# SAMC21_Xplained_Pro_Arduino_Connectors.net
KiCad netlist of a schematic drawn in Altium Designer
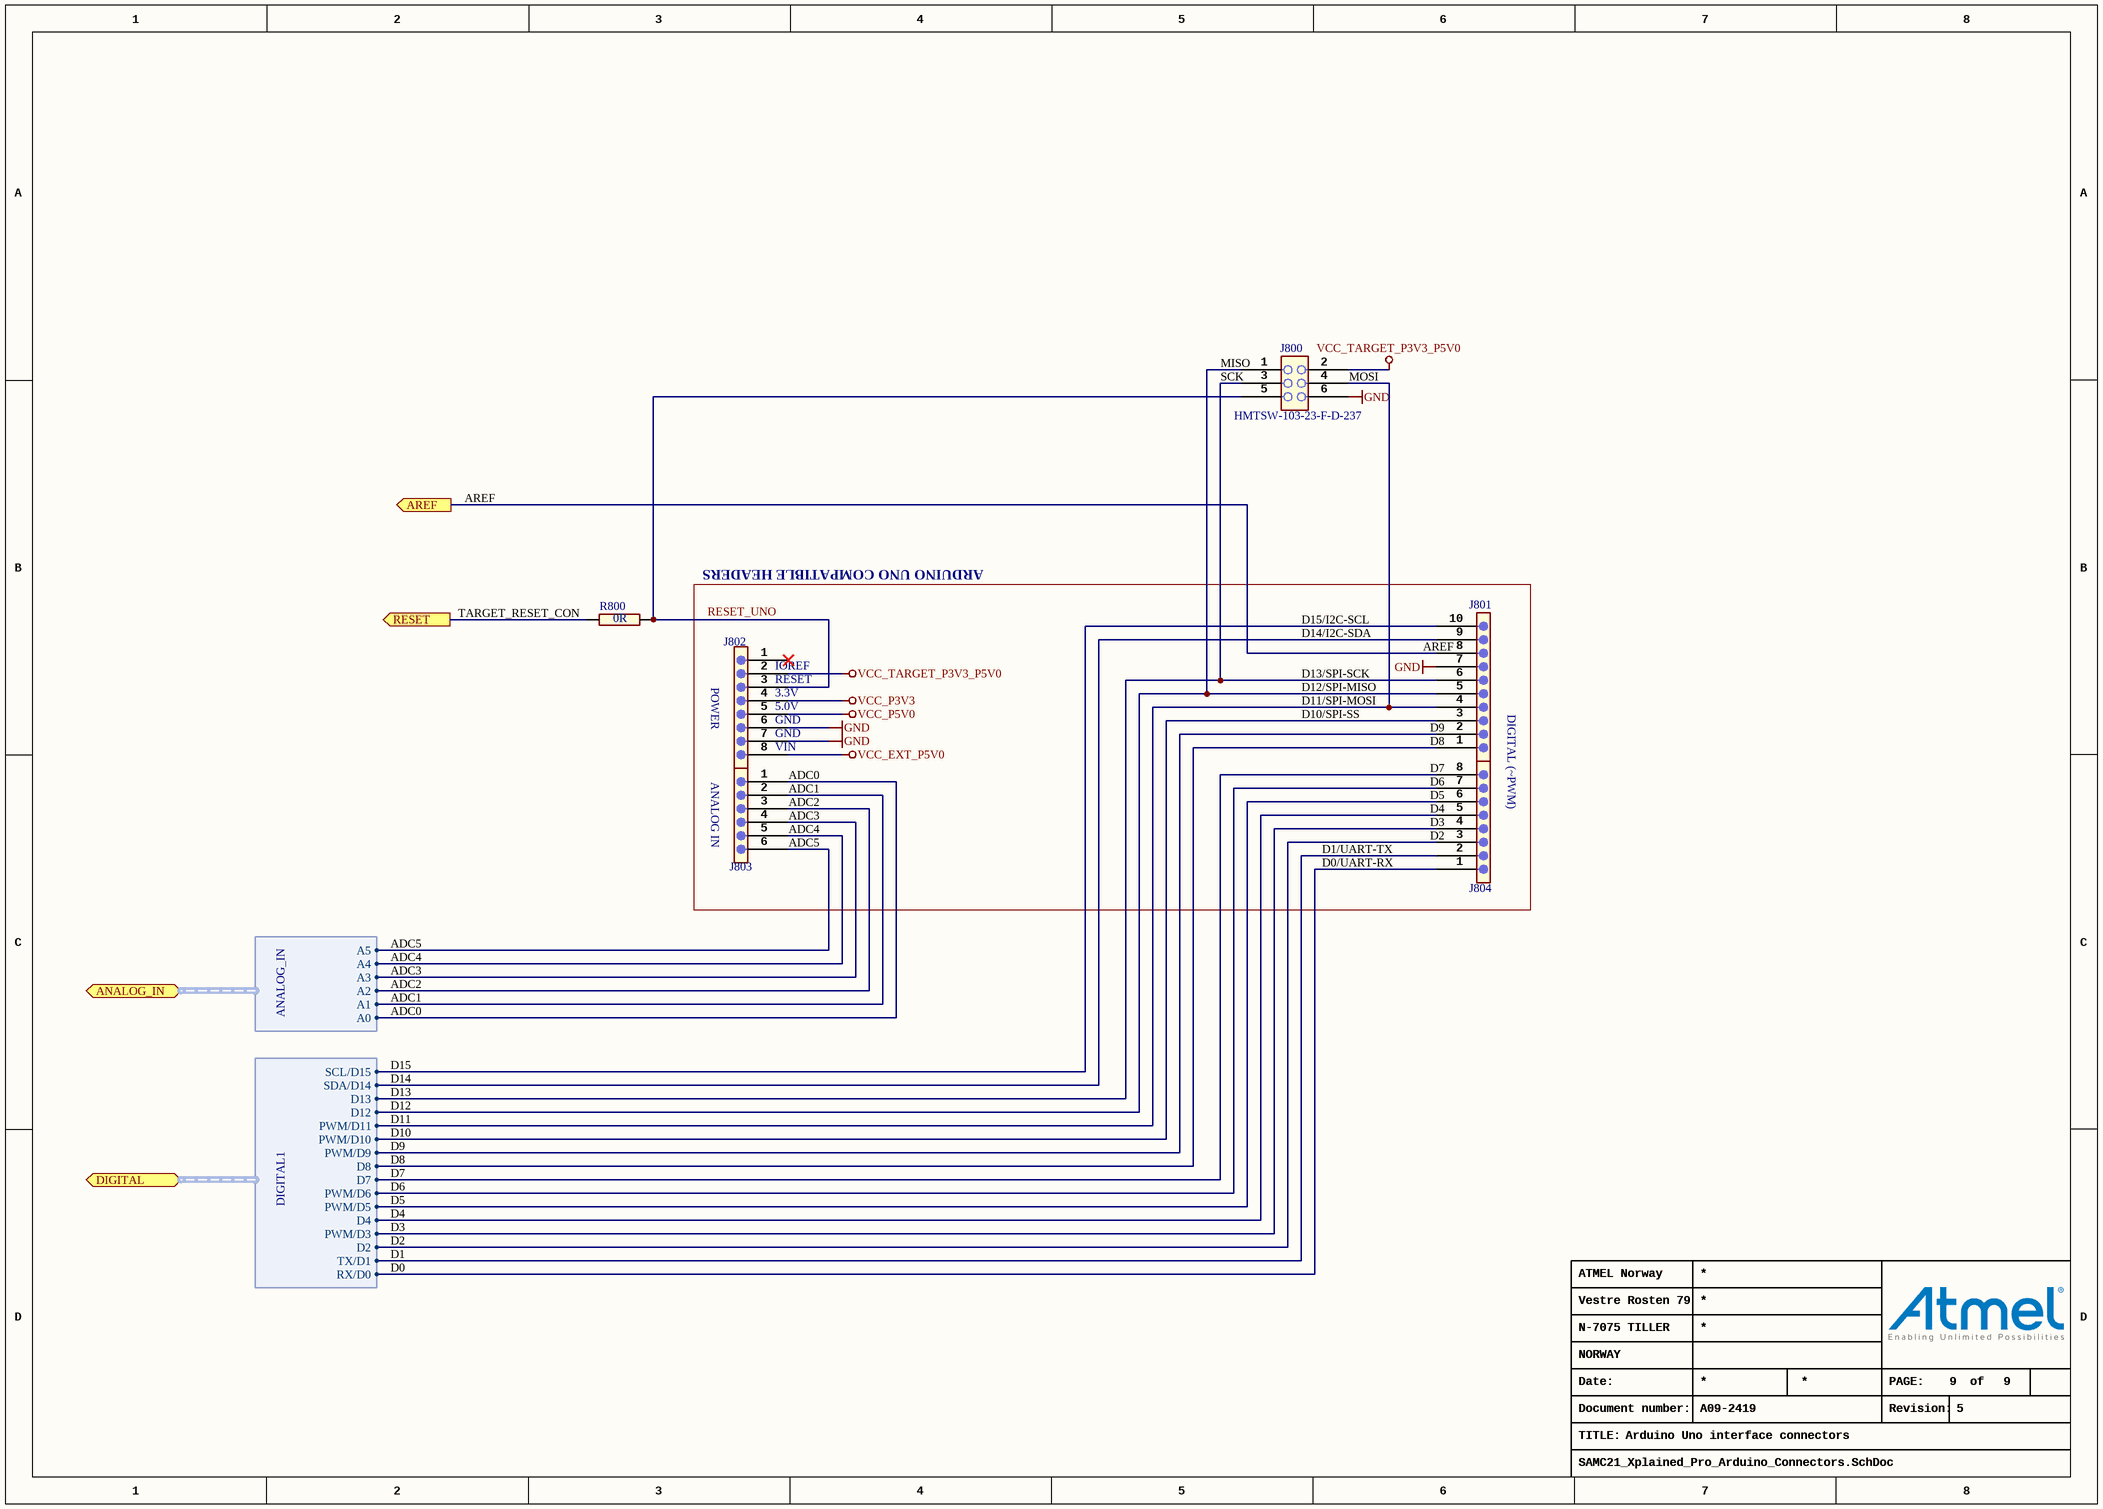
[diagram p0: SAMC21_Xplained_Pro_Arduino_Connectors.SchDoc]

(export (version "E")
  (design (tool "Eeschema 10.0.6"))
  (components
    (comp (ref "J800")
      (value "HMTSW-103-23-F-D-237")
      (footprint "AP8-00182")
      (description "2x3 pin header, 2.54mm pitch, Pin-in-Paste THM")
      (fields (field (name "MANUFACTURER") "SAMTEC"))
      (libsource (lib "AltiumDbLib") (part "HEADER 2x3"))
    )
    (comp (ref "J801")
      (value "~")
      (footprint "AP8-00822")
      (description "1x10 receptacle pin header, low insertion force, 2.54mm pitch THM, Pin in Paste")
      (fields (field (name "MANUFACTURER") "SAMTEC") (field (name "MPN") "SSQ-110-21-F-S"))
      (libsource (lib "AltiumDbLib") (part "HEADER 1x10 FEMALE"))
    )
    (comp (ref "J802")
      (value "~")
      (footprint "AP8-00823")
      (description "1x8 receptacle pin header, low insertion force, 2.54mm pitch THM, Pin in Paste")
      (fields (field (name "MANUFACTURER") "SAMTEC") (field (name "MPN") "SSQ-108-21-F-S"))
      (libsource (lib "") (part "HEADER 1x8 FEMALE_1"))
    )
    (comp (ref "J803")
      (value "~")
      (footprint "AP8-00824")
      (description "1x6 receptacle pin header, low insertion force, 2.54mm pitch THM")
      (fields (field (name "MANUFACTURER") "SAMTEC") (field (name "MPN") "SSQ-106-21-F-S"))
      (libsource (lib "AltiumDbLib") (part "HEADER 1x6 FEMALE"))
    )
    (comp (ref "J804")
      (value "~")
      (footprint "AP8-00823")
      (description "1x8 receptacle pin header, low insertion force, 2.54mm pitch THM, Pin in Paste")
      (fields (field (name "MANUFACTURER") "SAMTEC") (field (name "MPN") "SSQ-108-21-F-S"))
      (libsource (lib "AltiumDbLib") (part "HEADER 1x8 FEMALE"))
    )
    (comp (ref "R800")
      (value "0R")
      (footprint "AP2-00000")
      (description "RES 0.0 OHM 1/16W 0402 SMD")
      (fields (field (name "TOLERANCE") "1 %") (field (name "MANUFACTURER") "(n/a)"))
      (libsource (lib "AltiumDbLib") (part "R2"))
    )
  )
  (nets
    (net (code "3") (name "/A0") (class "Default")
      (node (ref "J803") (pin "1") (pinfunction "1_1") (pintype "passive"))
    )
    (net (code "4") (name "/A1") (class "Default")
      (node (ref "J803") (pin "2") (pinfunction "2_2") (pintype "passive"))
    )
    (net (code "5") (name "/A2") (class "Default")
      (node (ref "J803") (pin "3") (pinfunction "3_3") (pintype "passive"))
    )
    (net (code "6") (name "/A3") (class "Default")
      (node (ref "J803") (pin "4") (pinfunction "4_4") (pintype "passive"))
    )
    (net (code "7") (name "/A4") (class "Default")
      (node (ref "J803") (pin "5") (pinfunction "5_5") (pintype "passive"))
    )
    (net (code "8") (name "/A5") (class "Default")
      (node (ref "J803") (pin "6") (pinfunction "6_6") (pintype "passive"))
    )
    (net (code "9") (name "/AREF") (class "Default")
      (node (ref "J801") (pin "8") (pinfunction "8_8") (pintype "passive"))
    )
    (net (code "10") (name "/D2") (class "Default")
      (node (ref "J804") (pin "3") (pinfunction "3_3") (pintype "passive"))
    )
    (net (code "11") (name "/D4") (class "Default")
      (node (ref "J804") (pin "5") (pinfunction "5_5") (pintype "passive"))
    )
    (net (code "12") (name "/D7") (class "Default")
      (node (ref "J804") (pin "8") (pinfunction "8_8") (pintype "passive"))
    )
    (net (code "13") (name "/D8") (class "Default")
      (node (ref "J801") (pin "1") (pinfunction "1_1") (pintype "passive"))
    )
    (net (code "14") (name "/D12") (class "Default")
      (node (ref "J800") (pin "1") (pinfunction "1_1") (pintype "passive"))
      (node (ref "J801") (pin "5") (pinfunction "5_5") (pintype "passive"))
    )
    (net (code "15") (name "/D13") (class "Default")
      (node (ref "J800") (pin "3") (pinfunction "3_3") (pintype "passive"))
      (node (ref "J801") (pin "6") (pinfunction "6_6") (pintype "passive"))
    )
    (net (code "16") (name "/PWM{slash}D3") (class "Default")
      (node (ref "J804") (pin "4") (pinfunction "4_4") (pintype "passive"))
    )
    (net (code "17") (name "/PWM{slash}D5") (class "Default")
      (node (ref "J804") (pin "6") (pinfunction "6_6") (pintype "passive"))
    )
    (net (code "18") (name "/PWM{slash}D6") (class "Default")
      (node (ref "J804") (pin "7") (pinfunction "7_7") (pintype "passive"))
    )
    (net (code "19") (name "/PWM{slash}D9") (class "Default")
      (node (ref "J801") (pin "2") (pinfunction "2_2") (pintype "passive"))
    )
    (net (code "20") (name "/PWM{slash}D10") (class "Default")
      (node (ref "J801") (pin "3") (pinfunction "3_3") (pintype "passive"))
    )
    (net (code "21") (name "/PWM{slash}D11") (class "Default")
      (node (ref "J800") (pin "4") (pinfunction "4_4") (pintype "passive"))
      (node (ref "J801") (pin "4") (pinfunction "4_4") (pintype "passive"))
    )
    (net (code "22") (name "/RESET") (class "Default")
      (node (ref "R800") (pin "1") (pinfunction "1_1") (pintype "passive"))
    )
    (net (code "23") (name "/RESET_UNO") (class "Default")
      (node (ref "J800") (pin "5") (pinfunction "5_5") (pintype "passive"))
      (node (ref "J802") (pin "3") (pinfunction "3_3") (pintype "passive"))
      (node (ref "R800") (pin "2") (pinfunction "2_2") (pintype "passive"))
    )
    (net (code "24") (name "/RX{slash}D0") (class "Default")
      (node (ref "J804") (pin "1") (pinfunction "1_1") (pintype "passive"))
    )
    (net (code "25") (name "/SCL{slash}D15") (class "Default")
      (node (ref "J801") (pin "10") (pinfunction "10_10") (pintype "passive"))
    )
    (net (code "26") (name "/SDA{slash}D14") (class "Default")
      (node (ref "J801") (pin "9") (pinfunction "9_9") (pintype "passive"))
    )
    (net (code "27") (name "/TX{slash}D1") (class "Default")
      (node (ref "J804") (pin "2") (pinfunction "2_2") (pintype "passive"))
    )
    (net (code "30") (name "GND") (class "Default")
      (node (ref "J800") (pin "6") (pinfunction "6_6") (pintype "passive"))
      (node (ref "J801") (pin "7") (pinfunction "7_7") (pintype "passive"))
      (node (ref "J802") (pin "6") (pinfunction "6_6") (pintype "passive"))
      (node (ref "J802") (pin "7") (pinfunction "7_7") (pintype "passive"))
    )
    (net (code "31") (name "VCC_EXT_P5V0") (class "Default")
      (node (ref "J802") (pin "8") (pinfunction "8_8") (pintype "passive"))
    )
    (net (code "32") (name "VCC_P3V3") (class "Default")
      (node (ref "J802") (pin "4") (pinfunction "4_4") (pintype "passive"))
    )
    (net (code "33") (name "VCC_P5V0") (class "Default")
      (node (ref "J802") (pin "5") (pinfunction "5_5") (pintype "passive"))
    )
    (net (code "34") (name "VCC_TARGET_P3V3_P5V0") (class "Default")
      (node (ref "J800") (pin "2") (pinfunction "2_2") (pintype "passive"))
      (node (ref "J802") (pin "2") (pinfunction "2_2") (pintype "passive"))
    )
    (net (code "35") (name "unconnected-(J802-Pad1)") (class "Default")
      (node (ref "J802") (pin "1") (pinfunction "1_1") (pintype "passive+no_connect"))
    )
  )
)
